# TicTocTrac_top_v1_0.net
KiCad netlist of a schematic drawn in EAGLE
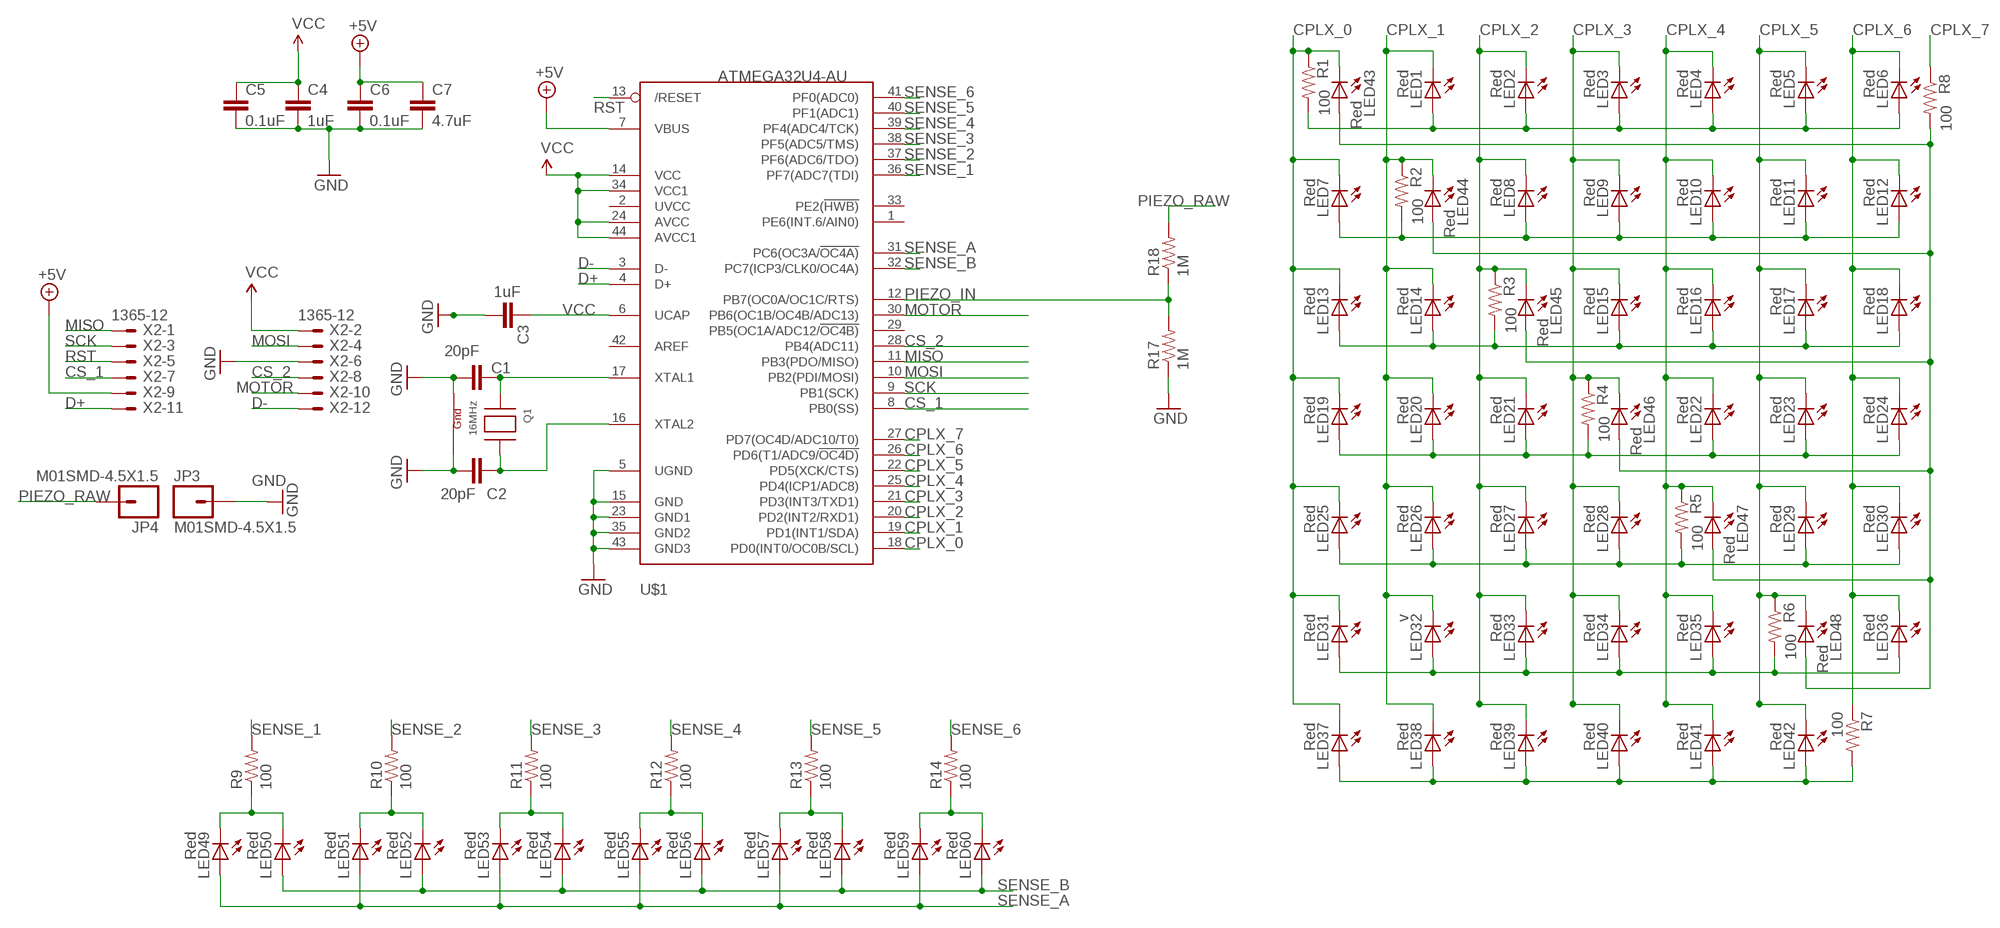
[diagram p0: schematic, sheet 1]

(export (version "E")
  (design (tool "Eeschema 10.0.6"))
  (components
    (comp (ref "C1")
      (value "20pF")
      (footprint "eagle-import:0402-CAP")
      (libsource (lib "eagle-import") (part "CAP0402-CAP"))
    )
    (comp (ref "C2")
      (value "20pF")
      (footprint "eagle-import:0402-CAP")
      (libsource (lib "eagle-import") (part "CAP0402-CAP"))
    )
    (comp (ref "C3")
      (value "1uF")
      (footprint "eagle-import:0402-CAP")
      (libsource (lib "eagle-import") (part "CAP0402-CAP"))
    )
    (comp (ref "C4")
      (value "1uF")
      (footprint "eagle-import:0402-CAP")
      (libsource (lib "eagle-import") (part "CAP0402-CAP"))
    )
    (comp (ref "C5")
      (value "0.1uF")
      (footprint "eagle-import:0402-CAP")
      (libsource (lib "eagle-import") (part "CAP0402-CAP"))
    )
    (comp (ref "C6")
      (value "0.1uF")
      (footprint "eagle-import:0402-CAP")
      (libsource (lib "eagle-import") (part "CAP0402-CAP"))
    )
    (comp (ref "C7")
      (value "4.7uF")
      (footprint "eagle-import:0402-CAP")
      (libsource (lib "eagle-import") (part "CAP0402-CAP"))
    )
    (comp (ref "JP3")
      (value "M01SMD-4.5X1.5")
      (footprint "eagle-import:PAD-1.5X4.5")
      (libsource (lib "eagle-import") (part "M01SMD-4.5X1.5"))
    )
    (comp (ref "JP4")
      (value "M01SMD-4.5X1.5")
      (footprint "eagle-import:PAD-1.5X4.5")
      (libsource (lib "eagle-import") (part "M01SMD-4.5X1.5"))
    )
    (comp (ref "LED1")
      (value "Red")
      (footprint "eagle-import:LED-0603")
      (libsource (lib "eagle-import") (part "LED0603"))
    )
    (comp (ref "LED2")
      (value "Red")
      (footprint "eagle-import:LED-0603")
      (libsource (lib "eagle-import") (part "LED0603"))
    )
    (comp (ref "LED3")
      (value "Red")
      (footprint "eagle-import:LED-0603")
      (libsource (lib "eagle-import") (part "LED0603"))
    )
    (comp (ref "LED4")
      (value "Red")
      (footprint "eagle-import:LED-0603")
      (libsource (lib "eagle-import") (part "LED0603"))
    )
    (comp (ref "LED5")
      (value "Red")
      (footprint "eagle-import:LED-0603")
      (libsource (lib "eagle-import") (part "LED0603"))
    )
    (comp (ref "LED6")
      (value "Red")
      (footprint "eagle-import:LED-0603")
      (libsource (lib "eagle-import") (part "LED0603"))
    )
    (comp (ref "LED7")
      (value "Red")
      (footprint "eagle-import:LED-0603")
      (libsource (lib "eagle-import") (part "LED0603"))
    )
    (comp (ref "LED8")
      (value "Red")
      (footprint "eagle-import:LED-0603")
      (libsource (lib "eagle-import") (part "LED0603"))
    )
    (comp (ref "LED9")
      (value "Red")
      (footprint "eagle-import:LED-0603")
      (libsource (lib "eagle-import") (part "LED0603"))
    )
    (comp (ref "LED10")
      (value "Red")
      (footprint "eagle-import:LED-0603")
      (libsource (lib "eagle-import") (part "LED0603"))
    )
    (comp (ref "LED11")
      (value "Red")
      (footprint "eagle-import:LED-0603")
      (libsource (lib "eagle-import") (part "LED0603"))
    )
    (comp (ref "LED12")
      (value "Red")
      (footprint "eagle-import:LED-0603")
      (libsource (lib "eagle-import") (part "LED0603"))
    )
    (comp (ref "LED13")
      (value "Red")
      (footprint "eagle-import:LED-0603")
      (libsource (lib "eagle-import") (part "LED0603"))
    )
    (comp (ref "LED14")
      (value "Red")
      (footprint "eagle-import:LED-0603")
      (libsource (lib "eagle-import") (part "LED0603"))
    )
    (comp (ref "LED15")
      (value "Red")
      (footprint "eagle-import:LED-0603")
      (libsource (lib "eagle-import") (part "LED0603"))
    )
    (comp (ref "LED16")
      (value "Red")
      (footprint "eagle-import:LED-0603")
      (libsource (lib "eagle-import") (part "LED0603"))
    )
    (comp (ref "LED17")
      (value "Red")
      (footprint "eagle-import:LED-0603")
      (libsource (lib "eagle-import") (part "LED0603"))
    )
    (comp (ref "LED18")
      (value "Red")
      (footprint "eagle-import:LED-0603")
      (libsource (lib "eagle-import") (part "LED0603"))
    )
    (comp (ref "LED19")
      (value "Red")
      (footprint "eagle-import:LED-0603")
      (libsource (lib "eagle-import") (part "LED0603"))
    )
    (comp (ref "LED20")
      (value "Red")
      (footprint "eagle-import:LED-0603")
      (libsource (lib "eagle-import") (part "LED0603"))
    )
    (comp (ref "LED21")
      (value "Red")
      (footprint "eagle-import:LED-0603")
      (libsource (lib "eagle-import") (part "LED0603"))
    )
    (comp (ref "LED22")
      (value "Red")
      (footprint "eagle-import:LED-0603")
      (libsource (lib "eagle-import") (part "LED0603"))
    )
    (comp (ref "LED23")
      (value "Red")
      (footprint "eagle-import:LED-0603")
      (libsource (lib "eagle-import") (part "LED0603"))
    )
    (comp (ref "LED24")
      (value "Red")
      (footprint "eagle-import:LED-0603")
      (libsource (lib "eagle-import") (part "LED0603"))
    )
    (comp (ref "LED25")
      (value "Red")
      (footprint "eagle-import:LED-0603")
      (libsource (lib "eagle-import") (part "LED0603"))
    )
    (comp (ref "LED26")
      (value "Red")
      (footprint "eagle-import:LED-0603")
      (libsource (lib "eagle-import") (part "LED0603"))
    )
    (comp (ref "LED27")
      (value "Red")
      (footprint "eagle-import:LED-0603")
      (libsource (lib "eagle-import") (part "LED0603"))
    )
    (comp (ref "LED28")
      (value "Red")
      (footprint "eagle-import:LED-0603")
      (libsource (lib "eagle-import") (part "LED0603"))
    )
    (comp (ref "LED29")
      (value "Red")
      (footprint "eagle-import:LED-0603")
      (libsource (lib "eagle-import") (part "LED0603"))
    )
    (comp (ref "LED30")
      (value "Red")
      (footprint "eagle-import:LED-0603")
      (libsource (lib "eagle-import") (part "LED0603"))
    )
    (comp (ref "LED31")
      (value "Red")
      (footprint "eagle-import:LED-0603")
      (libsource (lib "eagle-import") (part "LED0603"))
    )
    (comp (ref "LED32")
      (value "v")
      (footprint "eagle-import:LED-0603")
      (libsource (lib "eagle-import") (part "LED0603"))
    )
    (comp (ref "LED33")
      (value "Red")
      (footprint "eagle-import:LED-0603")
      (libsource (lib "eagle-import") (part "LED0603"))
    )
    (comp (ref "LED34")
      (value "Red")
      (footprint "eagle-import:LED-0603")
      (libsource (lib "eagle-import") (part "LED0603"))
    )
    (comp (ref "LED35")
      (value "Red")
      (footprint "eagle-import:LED-0603")
      (libsource (lib "eagle-import") (part "LED0603"))
    )
    (comp (ref "LED36")
      (value "Red")
      (footprint "eagle-import:LED-0603")
      (libsource (lib "eagle-import") (part "LED0603"))
    )
    (comp (ref "LED37")
      (value "Red")
      (footprint "eagle-import:LED-0603")
      (libsource (lib "eagle-import") (part "LED0603"))
    )
    (comp (ref "LED38")
      (value "Red")
      (footprint "eagle-import:LED-0603")
      (libsource (lib "eagle-import") (part "LED0603"))
    )
    (comp (ref "LED39")
      (value "Red")
      (footprint "eagle-import:LED-0603")
      (libsource (lib "eagle-import") (part "LED0603"))
    )
    (comp (ref "LED40")
      (value "Red")
      (footprint "eagle-import:LED-0603")
      (libsource (lib "eagle-import") (part "LED0603"))
    )
    (comp (ref "LED41")
      (value "Red")
      (footprint "eagle-import:LED-0603")
      (libsource (lib "eagle-import") (part "LED0603"))
    )
    (comp (ref "LED42")
      (value "Red")
      (footprint "eagle-import:LED-0603")
      (libsource (lib "eagle-import") (part "LED0603"))
    )
    (comp (ref "LED43")
      (value "Red")
      (footprint "eagle-import:LED-0603")
      (libsource (lib "eagle-import") (part "LED0603"))
    )
    (comp (ref "LED44")
      (value "Red")
      (footprint "eagle-import:LED-0603")
      (libsource (lib "eagle-import") (part "LED0603"))
    )
    (comp (ref "LED45")
      (value "Red")
      (footprint "eagle-import:LED-0603")
      (libsource (lib "eagle-import") (part "LED0603"))
    )
    (comp (ref "LED46")
      (value "Red")
      (footprint "eagle-import:LED-0603")
      (libsource (lib "eagle-import") (part "LED0603"))
    )
    (comp (ref "LED47")
      (value "Red")
      (footprint "eagle-import:LED-0603")
      (libsource (lib "eagle-import") (part "LED0603"))
    )
    (comp (ref "LED48")
      (value "Red")
      (footprint "eagle-import:LED-0603")
      (libsource (lib "eagle-import") (part "LED0603"))
    )
    (comp (ref "LED49")
      (value "Red")
      (footprint "eagle-import:LED-0603")
      (libsource (lib "eagle-import") (part "LED0603"))
    )
    (comp (ref "LED50")
      (value "Red")
      (footprint "eagle-import:LED-0603")
      (libsource (lib "eagle-import") (part "LED0603"))
    )
    (comp (ref "LED51")
      (value "Red")
      (footprint "eagle-import:LED-0603")
      (libsource (lib "eagle-import") (part "LED0603"))
    )
    (comp (ref "LED52")
      (value "Red")
      (footprint "eagle-import:LED-0603")
      (libsource (lib "eagle-import") (part "LED0603"))
    )
    (comp (ref "LED53")
      (value "Red")
      (footprint "eagle-import:LED-0603")
      (libsource (lib "eagle-import") (part "LED0603"))
    )
    (comp (ref "LED54")
      (value "Red")
      (footprint "eagle-import:LED-0603")
      (libsource (lib "eagle-import") (part "LED0603"))
    )
    (comp (ref "LED55")
      (value "Red")
      (footprint "eagle-import:LED-0603")
      (libsource (lib "eagle-import") (part "LED0603"))
    )
    (comp (ref "LED56")
      (value "Red")
      (footprint "eagle-import:LED-0603")
      (libsource (lib "eagle-import") (part "LED0603"))
    )
    (comp (ref "LED57")
      (value "Red")
      (footprint "eagle-import:LED-0603")
      (libsource (lib "eagle-import") (part "LED0603"))
    )
    (comp (ref "LED58")
      (value "Red")
      (footprint "eagle-import:LED-0603")
      (libsource (lib "eagle-import") (part "LED0603"))
    )
    (comp (ref "LED59")
      (value "Red")
      (footprint "eagle-import:LED-0603")
      (libsource (lib "eagle-import") (part "LED0603"))
    )
    (comp (ref "LED60")
      (value "Red")
      (footprint "eagle-import:LED-0603")
      (libsource (lib "eagle-import") (part "LED0603"))
    )
    (comp (ref "Q1")
      (value "16MHz")
      (footprint "eagle-import:NX3225")
      (libsource (lib "eagle-import") (part "XTAL-4-3225"))
    )
    (comp (ref "R1")
      (value "100")
      (footprint "eagle-import:0402-RES")
      (libsource (lib "eagle-import") (part "RESISTOR0402-RES"))
    )
    (comp (ref "R2")
      (value "100")
      (footprint "eagle-import:0402-RES")
      (libsource (lib "eagle-import") (part "RESISTOR0402-RES"))
    )
    (comp (ref "R3")
      (value "100")
      (footprint "eagle-import:0402-RES")
      (libsource (lib "eagle-import") (part "RESISTOR0402-RES"))
    )
    (comp (ref "R4")
      (value "100")
      (footprint "eagle-import:0402-RES")
      (libsource (lib "eagle-import") (part "RESISTOR0402-RES"))
    )
    (comp (ref "R5")
      (value "100")
      (footprint "eagle-import:0402-RES")
      (libsource (lib "eagle-import") (part "RESISTOR0402-RES"))
    )
    (comp (ref "R6")
      (value "100")
      (footprint "eagle-import:0402-RES")
      (libsource (lib "eagle-import") (part "RESISTOR0402-RES"))
    )
    (comp (ref "R7")
      (value "100")
      (footprint "eagle-import:0402-RES")
      (libsource (lib "eagle-import") (part "RESISTOR0402-RES"))
    )
    (comp (ref "R8")
      (value "100")
      (footprint "eagle-import:0402-RES")
      (libsource (lib "eagle-import") (part "RESISTOR0402-RES"))
    )
    (comp (ref "R9")
      (value "100")
      (footprint "eagle-import:0402-RES")
      (libsource (lib "eagle-import") (part "RESISTOR0402-RES"))
    )
    (comp (ref "R10")
      (value "100")
      (footprint "eagle-import:0402-RES")
      (libsource (lib "eagle-import") (part "RESISTOR0402-RES"))
    )
    (comp (ref "R11")
      (value "100")
      (footprint "eagle-import:0402-RES")
      (libsource (lib "eagle-import") (part "RESISTOR0402-RES"))
    )
    (comp (ref "R12")
      (value "100")
      (footprint "eagle-import:0402-RES")
      (libsource (lib "eagle-import") (part "RESISTOR0402-RES"))
    )
    (comp (ref "R13")
      (value "100")
      (footprint "eagle-import:0402-RES")
      (libsource (lib "eagle-import") (part "RESISTOR0402-RES"))
    )
    (comp (ref "R14")
      (value "100")
      (footprint "eagle-import:0402-RES")
      (libsource (lib "eagle-import") (part "RESISTOR0402-RES"))
    )
    (comp (ref "R17")
      (value "1M")
      (footprint "eagle-import:0805")
      (libsource (lib "eagle-import") (part "RESISTOR0805-RES"))
    )
    (comp (ref "R18")
      (value "1M")
      (footprint "eagle-import:0805")
      (libsource (lib "eagle-import") (part "RESISTOR0805-RES"))
    )
    (comp (ref "U$1")
      (value "ATMEGA32U4-AU")
      (footprint "eagle-import:TQFP44")
      (libsource (lib "eagle-import") (part "ATMEGA32U4-AU"))
    )
    (comp (ref "X2")
      (value "1365-12")
      (footprint "eagle-import:1365-12")
      (libsource (lib "eagle-import") (part "1365-12"))
    )
  )
  (nets
    (net (code "1") (name "+5V") (class "Default")
      (node (ref "C6") (pin "1") (pinfunction "1_1") (pintype "passive"))
      (node (ref "C7") (pin "1") (pinfunction "1_1") (pintype "passive"))
      (node (ref "U$1") (pin "7") (pinfunction "VBUS_7") (pintype "bidirectional"))
      (node (ref "X2") (pin "9") (pinfunction "S_9") (pintype "passive"))
    )
    (net (code "2") (name "/CPLX_0") (class "Default")
      (node (ref "LED13") (pin "C") (pinfunction "C_C") (pintype "passive"))
      (node (ref "LED19") (pin "C") (pinfunction "C_C") (pintype "passive"))
      (node (ref "LED25") (pin "C") (pinfunction "C_C") (pintype "passive"))
      (node (ref "LED31") (pin "C") (pinfunction "C_C") (pintype "passive"))
      (node (ref "LED37") (pin "C") (pinfunction "C_C") (pintype "passive"))
      (node (ref "LED43") (pin "C") (pinfunction "C_C") (pintype "passive"))
      (node (ref "LED7") (pin "C") (pinfunction "C_C") (pintype "passive"))
      (node (ref "R1") (pin "1") (pinfunction "1_1") (pintype "passive"))
      (node (ref "U$1") (pin "18") (pinfunction "PD0(INT0/OC0B/SCL)_18") (pintype "bidirectional"))
    )
    (net (code "3") (name "/CPLX_1") (class "Default")
      (node (ref "LED1") (pin "C") (pinfunction "C_C") (pintype "passive"))
      (node (ref "LED14") (pin "C") (pinfunction "C_C") (pintype "passive"))
      (node (ref "LED20") (pin "C") (pinfunction "C_C") (pintype "passive"))
      (node (ref "LED26") (pin "C") (pinfunction "C_C") (pintype "passive"))
      (node (ref "LED32") (pin "C") (pinfunction "C_C") (pintype "passive"))
      (node (ref "LED38") (pin "C") (pinfunction "C_C") (pintype "passive"))
      (node (ref "LED44") (pin "C") (pinfunction "C_C") (pintype "passive"))
      (node (ref "R2") (pin "1") (pinfunction "1_1") (pintype "passive"))
      (node (ref "U$1") (pin "19") (pinfunction "PD1(INT1/SDA)_19") (pintype "bidirectional"))
    )
    (net (code "4") (name "/CPLX_2") (class "Default")
      (node (ref "LED2") (pin "C") (pinfunction "C_C") (pintype "passive"))
      (node (ref "LED21") (pin "C") (pinfunction "C_C") (pintype "passive"))
      (node (ref "LED27") (pin "C") (pinfunction "C_C") (pintype "passive"))
      (node (ref "LED33") (pin "C") (pinfunction "C_C") (pintype "passive"))
      (node (ref "LED39") (pin "C") (pinfunction "C_C") (pintype "passive"))
      (node (ref "LED45") (pin "C") (pinfunction "C_C") (pintype "passive"))
      (node (ref "LED8") (pin "C") (pinfunction "C_C") (pintype "passive"))
      (node (ref "R3") (pin "1") (pinfunction "1_1") (pintype "passive"))
      (node (ref "U$1") (pin "20") (pinfunction "PD2(INT2/RXD1)_20") (pintype "bidirectional"))
    )
    (net (code "5") (name "/CPLX_3") (class "Default")
      (node (ref "LED15") (pin "C") (pinfunction "C_C") (pintype "passive"))
      (node (ref "LED28") (pin "C") (pinfunction "C_C") (pintype "passive"))
      (node (ref "LED3") (pin "C") (pinfunction "C_C") (pintype "passive"))
      (node (ref "LED34") (pin "C") (pinfunction "C_C") (pintype "passive"))
      (node (ref "LED40") (pin "C") (pinfunction "C_C") (pintype "passive"))
      (node (ref "LED46") (pin "C") (pinfunction "C_C") (pintype "passive"))
      (node (ref "LED9") (pin "C") (pinfunction "C_C") (pintype "passive"))
      (node (ref "R4") (pin "1") (pinfunction "1_1") (pintype "passive"))
      (node (ref "U$1") (pin "21") (pinfunction "PD3(INT3/TXD1)_21") (pintype "bidirectional"))
    )
    (net (code "6") (name "/CPLX_4") (class "Default")
      (node (ref "LED10") (pin "C") (pinfunction "C_C") (pintype "passive"))
      (node (ref "LED16") (pin "C") (pinfunction "C_C") (pintype "passive"))
      (node (ref "LED22") (pin "C") (pinfunction "C_C") (pintype "passive"))
      (node (ref "LED35") (pin "C") (pinfunction "C_C") (pintype "passive"))
      (node (ref "LED4") (pin "C") (pinfunction "C_C") (pintype "passive"))
      (node (ref "LED41") (pin "C") (pinfunction "C_C") (pintype "passive"))
      (node (ref "LED47") (pin "C") (pinfunction "C_C") (pintype "passive"))
      (node (ref "R5") (pin "1") (pinfunction "1_1") (pintype "passive"))
      (node (ref "U$1") (pin "25") (pinfunction "PD4(ICP1/ADC8)_25") (pintype "bidirectional"))
    )
    (net (code "7") (name "/CPLX_5") (class "Default")
      (node (ref "LED11") (pin "C") (pinfunction "C_C") (pintype "passive"))
      (node (ref "LED17") (pin "C") (pinfunction "C_C") (pintype "passive"))
      (node (ref "LED23") (pin "C") (pinfunction "C_C") (pintype "passive"))
      (node (ref "LED29") (pin "C") (pinfunction "C_C") (pintype "passive"))
      (node (ref "LED42") (pin "C") (pinfunction "C_C") (pintype "passive"))
      (node (ref "LED48") (pin "C") (pinfunction "C_C") (pintype "passive"))
      (node (ref "LED5") (pin "C") (pinfunction "C_C") (pintype "passive"))
      (node (ref "R6") (pin "1") (pinfunction "1_1") (pintype "passive"))
      (node (ref "U$1") (pin "22") (pinfunction "PD5(XCK/CTS)_22") (pintype "bidirectional"))
    )
    (net (code "8") (name "/CPLX_6") (class "Default")
      (node (ref "LED12") (pin "C") (pinfunction "C_C") (pintype "passive"))
      (node (ref "LED18") (pin "C") (pinfunction "C_C") (pintype "passive"))
      (node (ref "LED24") (pin "C") (pinfunction "C_C") (pintype "passive"))
      (node (ref "LED30") (pin "C") (pinfunction "C_C") (pintype "passive"))
      (node (ref "LED36") (pin "C") (pinfunction "C_C") (pintype "passive"))
      (node (ref "LED6") (pin "C") (pinfunction "C_C") (pintype "passive"))
      (node (ref "R7") (pin "1") (pinfunction "1_1") (pintype "passive"))
      (node (ref "U$1") (pin "26") (pinfunction "PD6(T1/ADC9/~{OC4D})_26") (pintype "bidirectional"))
    )
    (net (code "9") (name "/CPLX_7") (class "Default")
      (node (ref "R8") (pin "1") (pinfunction "1_1") (pintype "passive"))
      (node (ref "U$1") (pin "27") (pinfunction "PD7(OC4D/ADC10/T0)_27") (pintype "bidirectional"))
    )
    (net (code "10") (name "/CS_1") (class "Default")
      (node (ref "U$1") (pin "8") (pinfunction "PB0(SS)_8") (pintype "bidirectional"))
      (node (ref "X2") (pin "7") (pinfunction "S_7") (pintype "passive"))
    )
    (net (code "11") (name "/CS_2") (class "Default")
      (node (ref "U$1") (pin "28") (pinfunction "PB4(ADC11)_28") (pintype "bidirectional"))
      (node (ref "X2") (pin "8") (pinfunction "S_8") (pintype "passive"))
    )
    (net (code "12") (name "/D+") (class "Default")
      (node (ref "U$1") (pin "4") (pinfunction "D+_4") (pintype "bidirectional"))
      (node (ref "X2") (pin "11") (pinfunction "S_11") (pintype "passive"))
    )
    (net (code "13") (name "/D-") (class "Default")
      (node (ref "U$1") (pin "3") (pinfunction "D-_3") (pintype "bidirectional"))
      (node (ref "X2") (pin "12") (pinfunction "S_12") (pintype "passive"))
    )
    (net (code "14") (name "/MISO") (class "Default")
      (node (ref "U$1") (pin "11") (pinfunction "PB3(PDO/MISO)_11") (pintype "bidirectional"))
      (node (ref "X2") (pin "1") (pinfunction "S_1") (pintype "passive"))
    )
    (net (code "15") (name "/MOSI") (class "Default")
      (node (ref "U$1") (pin "10") (pinfunction "PB2(PDI/MOSI)_10") (pintype "bidirectional"))
      (node (ref "X2") (pin "4") (pinfunction "S_4") (pintype "passive"))
    )
    (net (code "16") (name "/MOTOR") (class "Default")
      (node (ref "U$1") (pin "30") (pinfunction "PB6(OC1B/OC4B/ADC13)_30") (pintype "bidirectional"))
      (node (ref "X2") (pin "10") (pinfunction "S_10") (pintype "passive"))
    )
    (net (code "17") (name "/PIEZO_IN") (class "Default")
      (node (ref "R17") (pin "2") (pinfunction "2_2") (pintype "passive"))
      (node (ref "R18") (pin "1") (pinfunction "1_1") (pintype "passive"))
      (node (ref "U$1") (pin "12") (pinfunction "PB7(OC0A/OC1C/RTS)_12") (pintype "bidirectional"))
    )
    (net (code "18") (name "/PIEZO_RAW") (class "Default")
      (node (ref "JP4") (pin "P$1") (pinfunction "1_P$1") (pintype "passive"))
      (node (ref "R18") (pin "2") (pinfunction "2_2") (pintype "passive"))
    )
    (net (code "19") (name "/RST") (class "Default")
      (node (ref "U$1") (pin "13") (pinfunction "/RESET_13") (pintype "bidirectional"))
      (node (ref "X2") (pin "5") (pinfunction "S_5") (pintype "passive"))
    )
    (net (code "20") (name "/SCK") (class "Default")
      (node (ref "U$1") (pin "9") (pinfunction "PB1(SCK)_9") (pintype "bidirectional"))
      (node (ref "X2") (pin "3") (pinfunction "S_3") (pintype "passive"))
    )
    (net (code "21") (name "/SENSE_1") (class "Default")
      (node (ref "R9") (pin "2") (pinfunction "2_2") (pintype "passive"))
      (node (ref "U$1") (pin "36") (pinfunction "PF7(ADC7(TDI)_36") (pintype "bidirectional"))
    )
    (net (code "22") (name "/SENSE_2") (class "Default")
      (node (ref "R10") (pin "2") (pinfunction "2_2") (pintype "passive"))
      (node (ref "U$1") (pin "37") (pinfunction "PF6(ADC6/TDO)_37") (pintype "bidirectional"))
    )
    (net (code "23") (name "/SENSE_3") (class "Default")
      (node (ref "R11") (pin "2") (pinfunction "2_2") (pintype "passive"))
      (node (ref "U$1") (pin "38") (pinfunction "PF5(ADC5/TMS)_38") (pintype "bidirectional"))
    )
    (net (code "24") (name "/SENSE_4") (class "Default")
      (node (ref "R12") (pin "2") (pinfunction "2_2") (pintype "passive"))
      (node (ref "U$1") (pin "39") (pinfunction "PF4(ADC4/TCK)_39") (pintype "bidirectional"))
    )
    (net (code "25") (name "/SENSE_5") (class "Default")
      (node (ref "R13") (pin "2") (pinfunction "2_2") (pintype "passive"))
      (node (ref "U$1") (pin "40") (pinfunction "PF1(ADC1)_40") (pintype "bidirectional"))
    )
    (net (code "26") (name "/SENSE_6") (class "Default")
      (node (ref "R14") (pin "2") (pinfunction "2_2") (pintype "passive"))
      (node (ref "U$1") (pin "41") (pinfunction "PF0(ADC0)_41") (pintype "bidirectional"))
    )
    (net (code "27") (name "/SENSE_A") (class "Default")
      (node (ref "LED49") (pin "A") (pinfunction "A_A") (pintype "passive"))
      (node (ref "LED51") (pin "A") (pinfunction "A_A") (pintype "passive"))
      (node (ref "LED53") (pin "A") (pinfunction "A_A") (pintype "passive"))
      (node (ref "LED55") (pin "A") (pinfunction "A_A") (pintype "passive"))
      (node (ref "LED57") (pin "A") (pinfunction "A_A") (pintype "passive"))
      (node (ref "LED59") (pin "A") (pinfunction "A_A") (pintype "passive"))
      (node (ref "U$1") (pin "31") (pinfunction "PC6(OC3A/~{OC4A})_31") (pintype "bidirectional"))
    )
    (net (code "28") (name "/SENSE_B") (class "Default")
      (node (ref "LED50") (pin "A") (pinfunction "A_A") (pintype "passive"))
      (node (ref "LED52") (pin "A") (pinfunction "A_A") (pintype "passive"))
      (node (ref "LED54") (pin "A") (pinfunction "A_A") (pintype "passive"))
      (node (ref "LED56") (pin "A") (pinfunction "A_A") (pintype "passive"))
      (node (ref "LED58") (pin "A") (pinfunction "A_A") (pintype "passive"))
      (node (ref "LED60") (pin "A") (pinfunction "A_A") (pintype "passive"))
      (node (ref "U$1") (pin "32") (pinfunction "PC7(ICP3/CLK0/OC4A)_32") (pintype "bidirectional"))
    )
    (net (code "29") (name "GND") (class "Default")
      (node (ref "C1") (pin "2") (pinfunction "2_2") (pintype "passive"))
      (node (ref "C2") (pin "2") (pinfunction "2_2") (pintype "passive"))
      (node (ref "C3") (pin "2") (pinfunction "2_2") (pintype "passive"))
      (node (ref "C4") (pin "2") (pinfunction "2_2") (pintype "passive"))
      (node (ref "C5") (pin "2") (pinfunction "2_2") (pintype "passive"))
      (node (ref "C6") (pin "2") (pinfunction "2_2") (pintype "passive"))
      (node (ref "C7") (pin "2") (pinfunction "2_2") (pintype "passive"))
      (node (ref "JP3") (pin "P$1") (pinfunction "1_P$1") (pintype "passive"))
      (node (ref "Q1") (pin "2") (pinfunction "G2_2") (pintype "power_in"))
      (node (ref "Q1") (pin "4") (pinfunction "G1_4") (pintype "power_in"))
      (node (ref "R17") (pin "1") (pinfunction "1_1") (pintype "passive"))
      (node (ref "U$1") (pin "15") (pinfunction "GND_15") (pintype "bidirectional"))
      (node (ref "U$1") (pin "23") (pinfunction "GND1_23") (pintype "bidirectional"))
      (node (ref "U$1") (pin "35") (pinfunction "GND2_35") (pintype "bidirectional"))
      (node (ref "U$1") (pin "43") (pinfunction "GND3_43") (pintype "bidirectional"))
      (node (ref "U$1") (pin "5") (pinfunction "UGND_5") (pintype "bidirectional"))
      (node (ref "X2") (pin "6") (pinfunction "S_6") (pintype "passive"))
    )
    (net (code "30") (name "Net-(LED1-PadA)") (class "Default")
      (node (ref "LED1") (pin "A") (pinfunction "A_A") (pintype "passive"))
      (node (ref "LED2") (pin "A") (pinfunction "A_A") (pintype "passive"))
      (node (ref "LED3") (pin "A") (pinfunction "A_A") (pintype "passive"))
      (node (ref "LED4") (pin "A") (pinfunction "A_A") (pintype "passive"))
      (node (ref "LED5") (pin "A") (pinfunction "A_A") (pintype "passive"))
      (node (ref "LED6") (pin "A") (pinfunction "A_A") (pintype "passive"))
      (node (ref "R1") (pin "2") (pinfunction "2_2") (pintype "passive"))
    )
    (net (code "31") (name "Net-(LED10-PadA)") (class "Default")
      (node (ref "LED10") (pin "A") (pinfunction "A_A") (pintype "passive"))
      (node (ref "LED11") (pin "A") (pinfunction "A_A") (pintype "passive"))
      (node (ref "LED12") (pin "A") (pinfunction "A_A") (pintype "passive"))
      (node (ref "LED7") (pin "A") (pinfunction "A_A") (pintype "passive"))
      (node (ref "LED8") (pin "A") (pinfunction "A_A") (pintype "passive"))
      (node (ref "LED9") (pin "A") (pinfunction "A_A") (pintype "passive"))
      (node (ref "R2") (pin "2") (pinfunction "2_2") (pintype "passive"))
    )
    (net (code "32") (name "Net-(LED13-PadA)") (class "Default")
      (node (ref "LED13") (pin "A") (pinfunction "A_A") (pintype "passive"))
      (node (ref "LED14") (pin "A") (pinfunction "A_A") (pintype "passive"))
      (node (ref "LED15") (pin "A") (pinfunction "A_A") (pintype "passive"))
      (node (ref "LED16") (pin "A") (pinfunction "A_A") (pintype "passive"))
      (node (ref "LED17") (pin "A") (pinfunction "A_A") (pintype "passive"))
      (node (ref "LED18") (pin "A") (pinfunction "A_A") (pintype "passive"))
      (node (ref "R3") (pin "2") (pinfunction "2_2") (pintype "passive"))
    )
    (net (code "33") (name "Net-(LED19-PadA)") (class "Default")
      (node (ref "LED19") (pin "A") (pinfunction "A_A") (pintype "passive"))
      (node (ref "LED20") (pin "A") (pinfunction "A_A") (pintype "passive"))
      (node (ref "LED21") (pin "A") (pinfunction "A_A") (pintype "passive"))
      (node (ref "LED22") (pin "A") (pinfunction "A_A") (pintype "passive"))
      (node (ref "LED23") (pin "A") (pinfunction "A_A") (pintype "passive"))
      (node (ref "LED24") (pin "A") (pinfunction "A_A") (pintype "passive"))
      (node (ref "R4") (pin "2") (pinfunction "2_2") (pintype "passive"))
    )
    (net (code "34") (name "Net-(LED25-PadA)") (class "Default")
      (node (ref "LED25") (pin "A") (pinfunction "A_A") (pintype "passive"))
      (node (ref "LED26") (pin "A") (pinfunction "A_A") (pintype "passive"))
      (node (ref "LED27") (pin "A") (pinfunction "A_A") (pintype "passive"))
      (node (ref "LED28") (pin "A") (pinfunction "A_A") (pintype "passive"))
      (node (ref "LED29") (pin "A") (pinfunction "A_A") (pintype "passive"))
      (node (ref "LED30") (pin "A") (pinfunction "A_A") (pintype "passive"))
      (node (ref "R5") (pin "2") (pinfunction "2_2") (pintype "passive"))
    )
    (net (code "35") (name "Net-(LED31-PadA)") (class "Default")
      (node (ref "LED31") (pin "A") (pinfunction "A_A") (pintype "passive"))
      (node (ref "LED32") (pin "A") (pinfunction "A_A") (pintype "passive"))
      (node (ref "LED33") (pin "A") (pinfunction "A_A") (pintype "passive"))
      (node (ref "LED34") (pin "A") (pinfunction "A_A") (pintype "passive"))
      (node (ref "LED35") (pin "A") (pinfunction "A_A") (pintype "passive"))
      (node (ref "LED36") (pin "A") (pinfunction "A_A") (pintype "passive"))
      (node (ref "R6") (pin "2") (pinfunction "2_2") (pintype "passive"))
    )
    (net (code "36") (name "Net-(LED37-PadA)") (class "Default")
      (node (ref "LED37") (pin "A") (pinfunction "A_A") (pintype "passive"))
      (node (ref "LED38") (pin "A") (pinfunction "A_A") (pintype "passive"))
      (node (ref "LED39") (pin "A") (pinfunction "A_A") (pintype "passive"))
      (node (ref "LED40") (pin "A") (pinfunction "A_A") (pintype "passive"))
      (node (ref "LED41") (pin "A") (pinfunction "A_A") (pintype "passive"))
      (node (ref "LED42") (pin "A") (pinfunction "A_A") (pintype "passive"))
      (node (ref "R7") (pin "2") (pinfunction "2_2") (pintype "passive"))
    )
    (net (code "37") (name "Net-(LED43-PadA)") (class "Default")
      (node (ref "LED43") (pin "A") (pinfunction "A_A") (pintype "passive"))
      (node (ref "LED44") (pin "A") (pinfunction "A_A") (pintype "passive"))
      (node (ref "LED45") (pin "A") (pinfunction "A_A") (pintype "passive"))
      (node (ref "LED46") (pin "A") (pinfunction "A_A") (pintype "passive"))
      (node (ref "LED47") (pin "A") (pinfunction "A_A") (pintype "passive"))
      (node (ref "LED48") (pin "A") (pinfunction "A_A") (pintype "passive"))
      (node (ref "R8") (pin "2") (pinfunction "2_2") (pintype "passive"))
    )
    (net (code "38") (name "Net-(LED49-PadC)") (class "Default")
      (node (ref "LED49") (pin "C") (pinfunction "C_C") (pintype "passive"))
      (node (ref "LED50") (pin "C") (pinfunction "C_C") (pintype "passive"))
      (node (ref "R9") (pin "1") (pinfunction "1_1") (pintype "passive"))
    )
    (net (code "39") (name "Net-(LED51-PadC)") (class "Default")
      (node (ref "LED51") (pin "C") (pinfunction "C_C") (pintype "passive"))
      (node (ref "LED52") (pin "C") (pinfunction "C_C") (pintype "passive"))
      (node (ref "R10") (pin "1") (pinfunction "1_1") (pintype "passive"))
    )
    (net (code "40") (name "Net-(LED53-PadC)") (class "Default")
      (node (ref "LED53") (pin "C") (pinfunction "C_C") (pintype "passive"))
      (node (ref "LED54") (pin "C") (pinfunction "C_C") (pintype "passive"))
      (node (ref "R11") (pin "1") (pinfunction "1_1") (pintype "passive"))
    )
    (net (code "41") (name "Net-(LED55-PadC)") (class "Default")
      (node (ref "LED55") (pin "C") (pinfunction "C_C") (pintype "passive"))
      (node (ref "LED56") (pin "C") (pinfunction "C_C") (pintype "passive"))
      (node (ref "R12") (pin "1") (pinfunction "1_1") (pintype "passive"))
    )
    (net (code "42") (name "Net-(LED57-PadC)") (class "Default")
      (node (ref "LED57") (pin "C") (pinfunction "C_C") (pintype "passive"))
      (node (ref "LED58") (pin "C") (pinfunction "C_C") (pintype "passive"))
      (node (ref "R13") (pin "1") (pinfunction "1_1") (pintype "passive"))
    )
    (net (code "43") (name "Net-(LED59-PadC)") (class "Default")
      (node (ref "LED59") (pin "C") (pinfunction "C_C") (pintype "passive"))
      (node (ref "LED60") (pin "C") (pinfunction "C_C") (pintype "passive"))
      (node (ref "R14") (pin "1") (pinfunction "1_1") (pintype "passive"))
    )
    (net (code "44") (name "Net-(Q1-X1)") (class "Default")
      (node (ref "C1") (pin "1") (pinfunction "1_1") (pintype "passive"))
      (node (ref "Q1") (pin "1") (pinfunction "X1_1") (pintype "bidirectional"))
      (node (ref "U$1") (pin "17") (pinfunction "XTAL1_17") (pintype "bidirectional"))
    )
    (net (code "45") (name "Net-(Q1-X2)") (class "Default")
      (node (ref "C2") (pin "1") (pinfunction "1_1") (pintype "passive"))
      (node (ref "Q1") (pin "3") (pinfunction "X2_3") (pintype "bidirectional"))
      (node (ref "U$1") (pin "16") (pinfunction "XTAL2_16") (pintype "bidirectional"))
    )
    (net (code "46") (name "VCC") (class "Default")
      (node (ref "C3") (pin "1") (pinfunction "1_1") (pintype "passive"))
      (node (ref "C4") (pin "1") (pinfunction "1_1") (pintype "passive"))
      (node (ref "C5") (pin "1") (pinfunction "1_1") (pintype "passive"))
      (node (ref "U$1") (pin "14") (pinfunction "VCC_14") (pintype "bidirectional"))
      (node (ref "U$1") (pin "24") (pinfunction "AVCC_24") (pintype "bidirectional"))
      (node (ref "U$1") (pin "34") (pinfunction "VCC1_34") (pintype "bidirectional"))
      (node (ref "U$1") (pin "44") (pinfunction "AVCC1_44") (pintype "bidirectional"))
      (node (ref "U$1") (pin "6") (pinfunction "UCAP_6") (pintype "bidirectional"))
      (node (ref "X2") (pin "2") (pinfunction "S_2") (pintype "passive"))
    )
    (net (code "47") (name "unconnected-(U$1-AREF-Pad42)") (class "Default")
      (node (ref "U$1") (pin "42") (pinfunction "AREF_42") (pintype "bidirectional"))
    )
    (net (code "48") (name "unconnected-(U$1-PB5(OC1A{slash}ADC12{slash}~{OC4B})-Pad29)") (class "Default")
      (node (ref "U$1") (pin "29") (pinfunction "PB5(OC1A/ADC12/~{OC4B})_29") (pintype "bidirectional"))
    )
    (net (code "49") (name "unconnected-(U$1-PE2(~{HWB})-Pad33)") (class "Default")
      (node (ref "U$1") (pin "33") (pinfunction "PE2(~{HWB})_33") (pintype "bidirectional"))
    )
    (net (code "50") (name "unconnected-(U$1-PE6(INT.6{slash}AIN0)-Pad1)") (class "Default")
      (node (ref "U$1") (pin "1") (pinfunction "PE6(INT.6/AIN0)_1") (pintype "bidirectional"))
    )
    (net (code "51") (name "unconnected-(U$1-UVCC-Pad2)") (class "Default")
      (node (ref "U$1") (pin "2") (pinfunction "UVCC_2") (pintype "bidirectional"))
    )
  )
)
